# DUObot.net
KiCad netlist of a schematic drawn in EAGLE
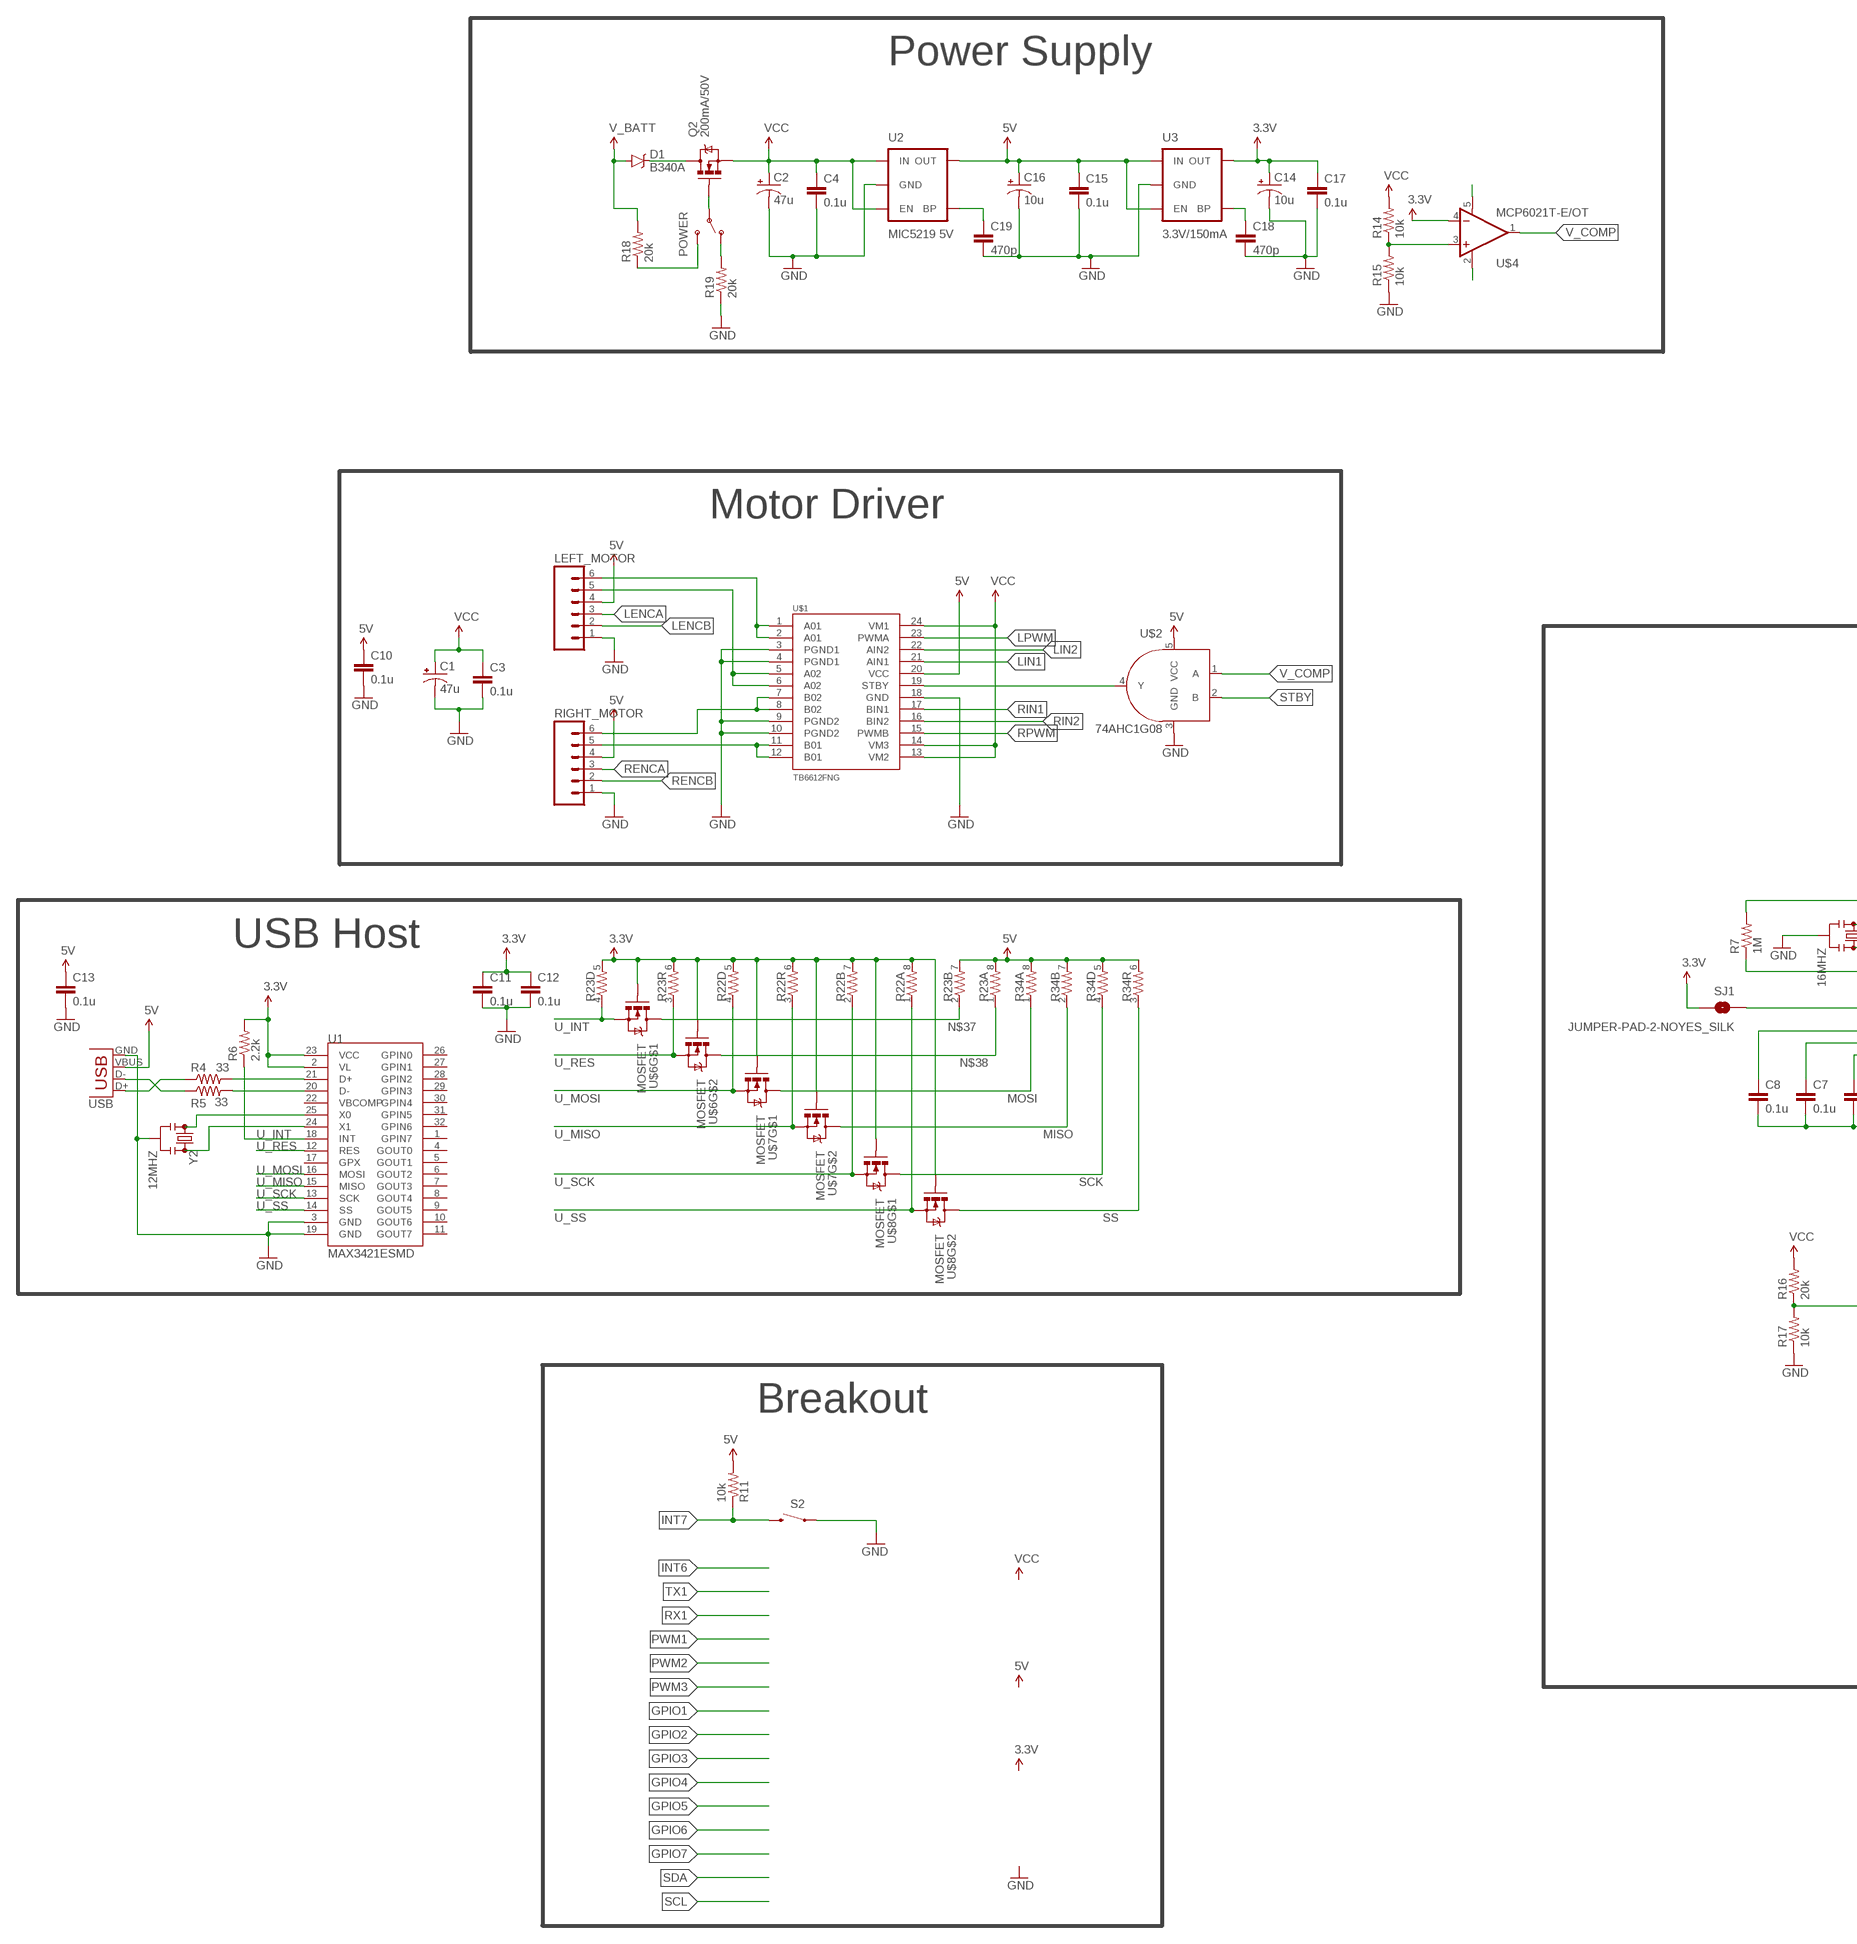
[diagram p0: schematic, sheet 1, part 1 of 2]
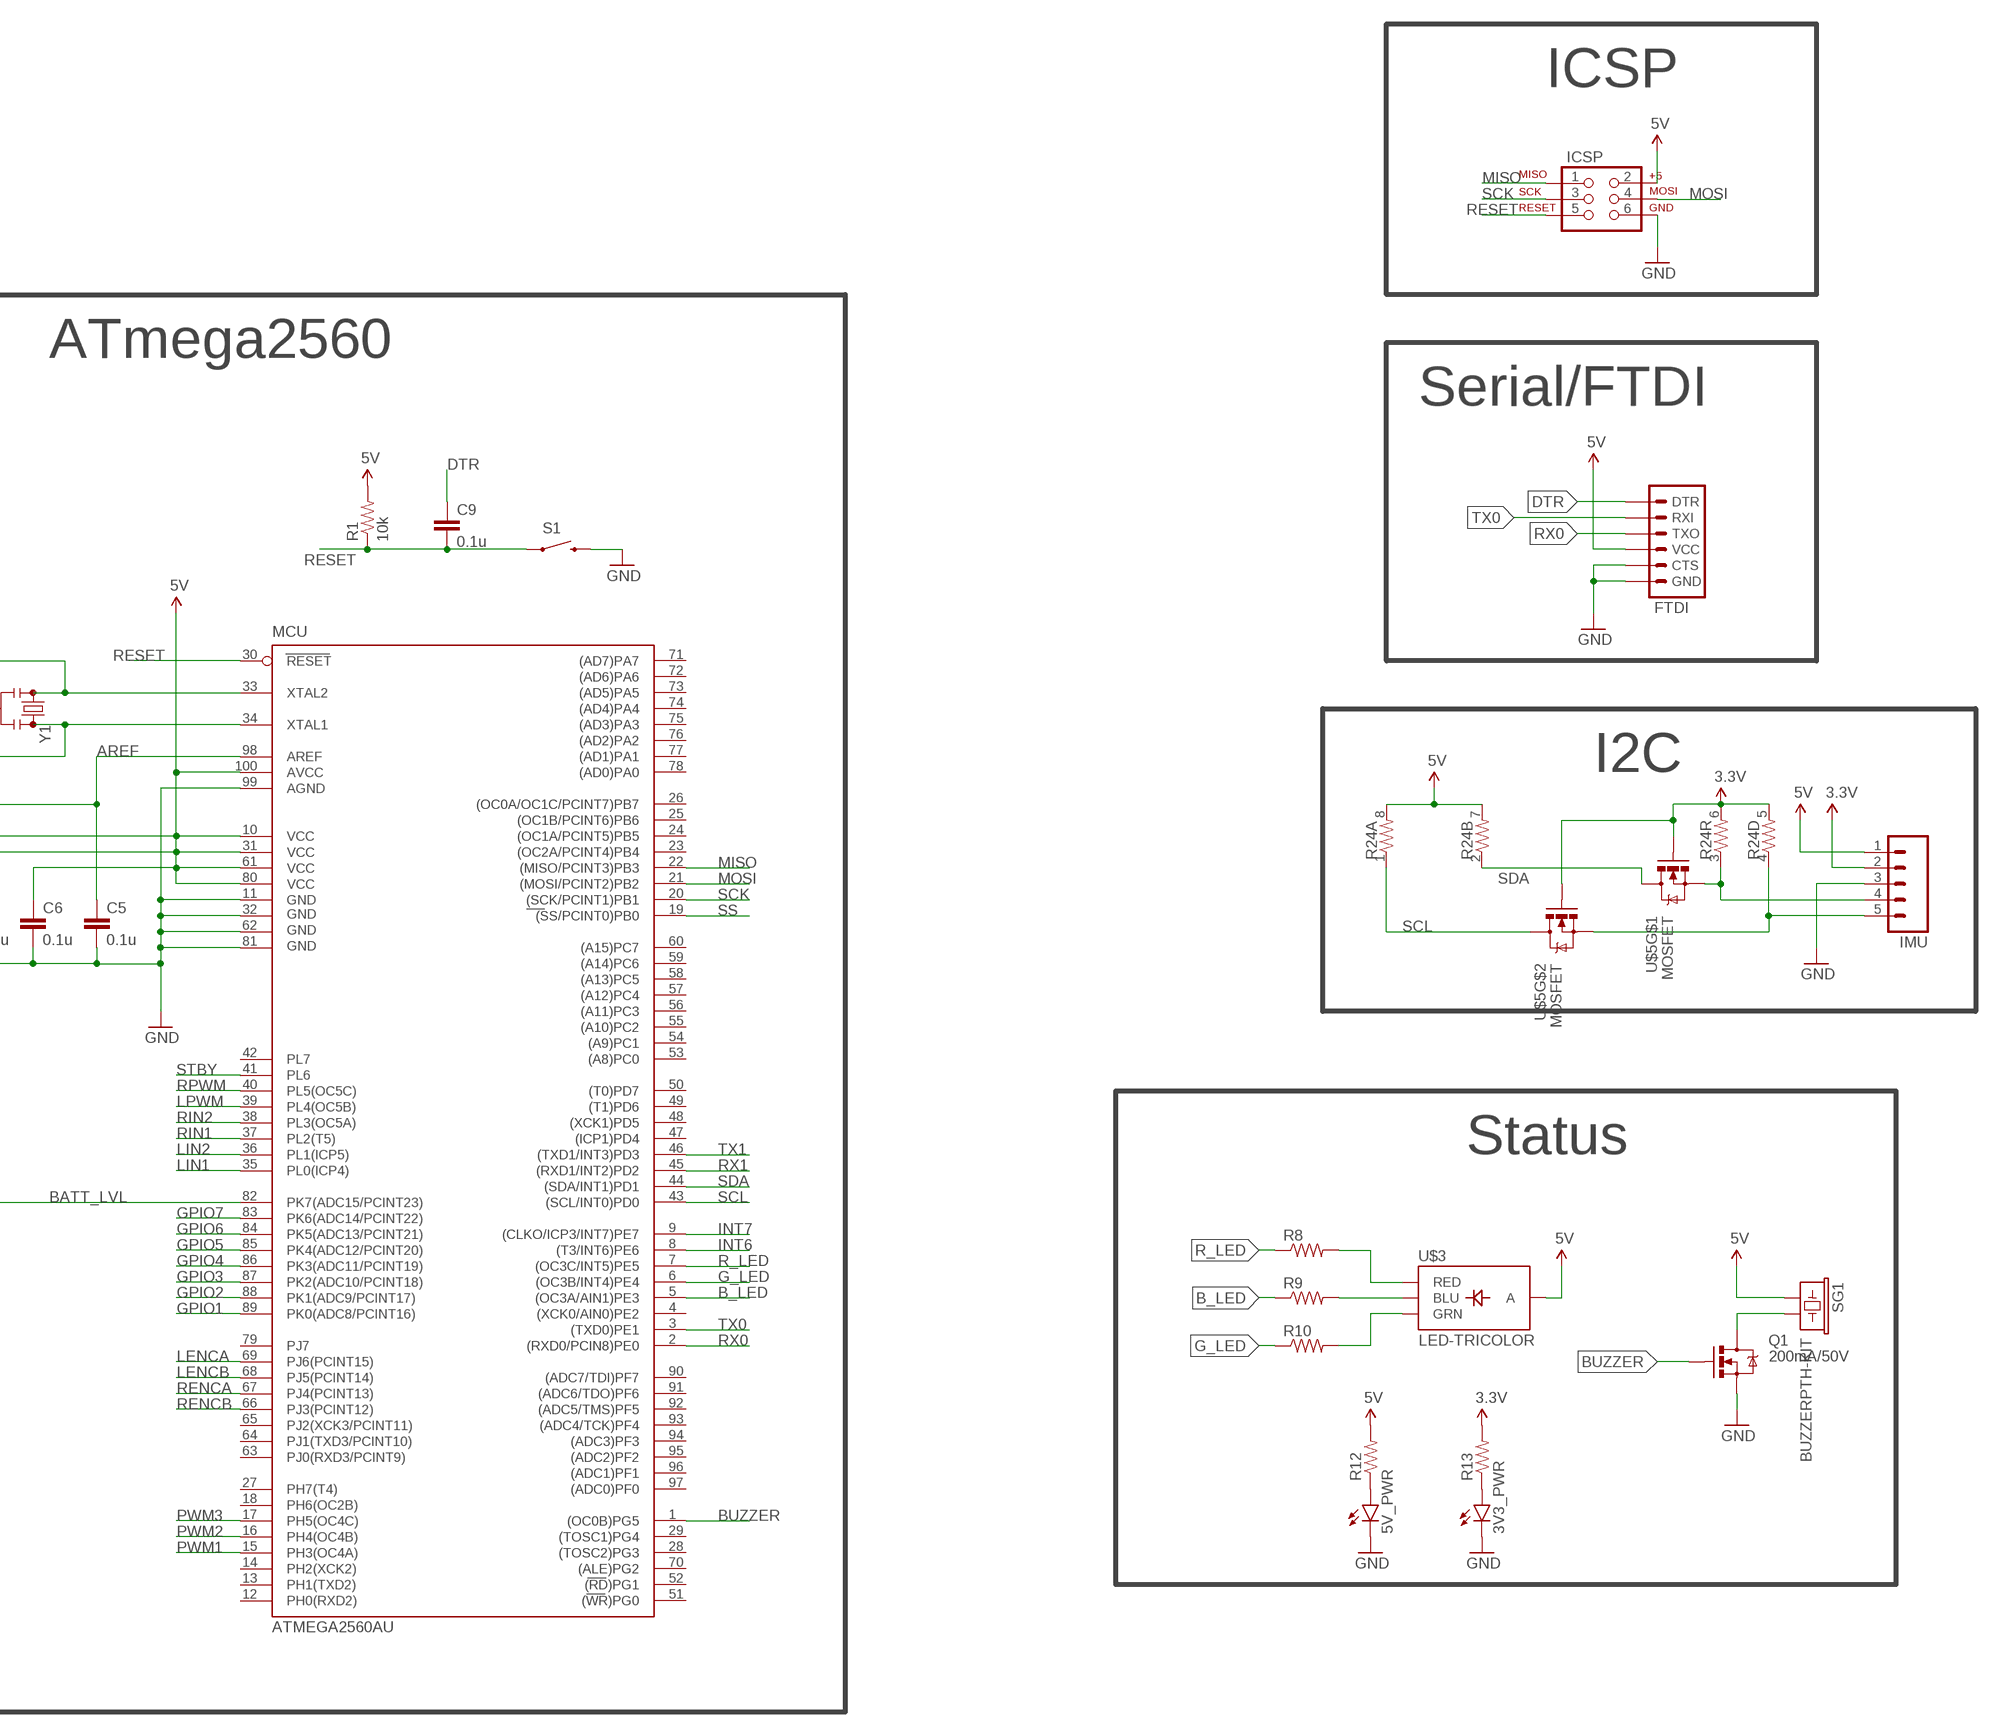
[diagram p1: schematic, sheet 1, part 2 of 2]

(export (version "E")
  (design (tool "Eeschema 10.0.6"))
  (components
    (comp (ref "3V3_PWR")
      (value "LED0805")
      (footprint "eagle-import:LED-0805")
      (libsource (lib "eagle-import") (part "LED0805"))
    )
    (comp (ref "5V_PWR")
      (value "LED0805")
      (footprint "eagle-import:LED-0805")
      (libsource (lib "eagle-import") (part "LED0805"))
    )
    (comp (ref "C1")
      (value "47u")
      (footprint "eagle-import:PANASONIC_D")
      (libsource (lib "eagle-import") (part "CAP_POLD"))
    )
    (comp (ref "C2")
      (value "47u")
      (footprint "eagle-import:PANASONIC_D")
      (libsource (lib "eagle-import") (part "CAP_POLD"))
    )
    (comp (ref "C3")
      (value "0.1u")
      (footprint "eagle-import:0805")
      (libsource (lib "eagle-import") (part "CAP0805"))
    )
    (comp (ref "C4")
      (value "0.1u")
      (footprint "eagle-import:0805")
      (libsource (lib "eagle-import") (part "CAP0805"))
    )
    (comp (ref "C5")
      (value "0.1u")
      (footprint "eagle-import:0805")
      (libsource (lib "eagle-import") (part "CAP0805"))
    )
    (comp (ref "C6")
      (value "0.1u")
      (footprint "eagle-import:0805")
      (libsource (lib "eagle-import") (part "CAP0805"))
    )
    (comp (ref "C7")
      (value "0.1u")
      (footprint "eagle-import:0805")
      (libsource (lib "eagle-import") (part "CAP0805"))
    )
    (comp (ref "C8")
      (value "0.1u")
      (footprint "eagle-import:0805")
      (libsource (lib "eagle-import") (part "CAP0805"))
    )
    (comp (ref "C9")
      (value "0.1u")
      (footprint "eagle-import:0805")
      (libsource (lib "eagle-import") (part "CAP0805"))
    )
    (comp (ref "C10")
      (value "0.1u")
      (footprint "eagle-import:0805")
      (libsource (lib "eagle-import") (part "CAP0805"))
    )
    (comp (ref "C11")
      (value "0.1u")
      (footprint "eagle-import:0805")
      (libsource (lib "eagle-import") (part "CAP0805"))
    )
    (comp (ref "C12")
      (value "0.1u")
      (footprint "eagle-import:0805")
      (libsource (lib "eagle-import") (part "CAP0805"))
    )
    (comp (ref "C13")
      (value "0.1u")
      (footprint "eagle-import:0805")
      (libsource (lib "eagle-import") (part "CAP0805"))
    )
    (comp (ref "C14")
      (value "10u")
      (footprint "eagle-import:EIA3216")
      (libsource (lib "eagle-import") (part "SparkFun-Passives_CAP_POL1206"))
    )
    (comp (ref "C15")
      (value "0.1u")
      (footprint "eagle-import:0805")
      (libsource (lib "eagle-import") (part "CAP0805"))
    )
    (comp (ref "C16")
      (value "10u")
      (footprint "eagle-import:EIA3216")
      (libsource (lib "eagle-import") (part "SparkFun-Passives_CAP_POL1206"))
    )
    (comp (ref "C17")
      (value "0.1u")
      (footprint "eagle-import:0805")
      (libsource (lib "eagle-import") (part "CAP0805"))
    )
    (comp (ref "C18")
      (value "470p")
      (footprint "eagle-import:0805")
      (libsource (lib "eagle-import") (part "CAP0805"))
    )
    (comp (ref "C19")
      (value "470p")
      (footprint "eagle-import:0805")
      (libsource (lib "eagle-import") (part "CAP0805"))
    )
    (comp (ref "D1")
      (value "B340A")
      (footprint "eagle-import:SMA-DIODE")
      (libsource (lib "eagle-import") (part "DIODE-SCHOTTKY-B340A"))
    )
    (comp (ref "FTDI")
      (value "ARDUINO_SERIAL_PROGRAMPTH")
      (footprint "eagle-import:1X06")
      (libsource (lib "eagle-import") (part "ARDUINO_SERIAL_PROGRAMPTH"))
    )
    (comp (ref "ICSP")
      (value "AVR_SPI_PRG_6TESTPOINTS")
      (footprint "eagle-import:2X3_TEST_POINTS")
      (libsource (lib "eagle-import") (part "AVR_SPI_PRG_6TESTPOINTS"))
    )
    (comp (ref "IMU")
      (value "M05SMD2")
      (footprint "eagle-import:1X05-1MM-RA")
      (libsource (lib "eagle-import") (part "M05SMD2"))
    )
    (comp (ref "LEFT_MOTOR")
      (value "M06SMD-1MM")
      (footprint "eagle-import:1X06-1MM")
      (libsource (lib "eagle-import") (part "M06SMD-1MM"))
    )
    (comp (ref "MCU")
      (value "ATMEGA2560AU")
      (footprint "eagle-import:TQFP100")
      (libsource (lib "eagle-import") (part "ATMEGA2560AU"))
    )
    (comp (ref "POWER")
      (value "SWITCH-SPDT-SMD-A")
      (footprint "eagle-import:SWITCH-SPST-SMD-A")
      (libsource (lib "eagle-import") (part "SWITCH-SPDT-SMD-A"))
    )
    (comp (ref "Q1")
      (value "200mA/50V")
      (footprint "eagle-import:SOT23-3")
      (libsource (lib "eagle-import") (part "MOSFET-NCHANNELBSS138"))
    )
    (comp (ref "Q2")
      (value "200mA/50V")
      (footprint "eagle-import:SOT23-3")
      (libsource (lib "eagle-import") (part "MOSFET-NCHANNELBSS138"))
    )
    (comp (ref "R1")
      (value "10k")
      (footprint "eagle-import:0805")
      (libsource (lib "eagle-import") (part "RESISTOR0805-RES"))
    )
    (comp (ref "R4")
      (value "33")
      (footprint "eagle-import:0805")
      (libsource (lib "eagle-import") (part "RESISTOR0805-RES"))
    )
    (comp (ref "R5")
      (value "33")
      (footprint "eagle-import:0805")
      (libsource (lib "eagle-import") (part "RESISTOR0805-RES"))
    )
    (comp (ref "R6")
      (value "2.2k")
      (footprint "eagle-import:0805")
      (libsource (lib "eagle-import") (part "RESISTOR0805-RES"))
    )
    (comp (ref "R7")
      (value "1M")
      (footprint "eagle-import:0805")
      (libsource (lib "eagle-import") (part "RESISTOR0805-RES"))
    )
    (comp (ref "R8")
      (value "RESISTOR0805-RES")
      (footprint "eagle-import:0805")
      (libsource (lib "eagle-import") (part "RESISTOR0805-RES"))
    )
    (comp (ref "R9")
      (value "RESISTOR0805-RES")
      (footprint "eagle-import:0805")
      (libsource (lib "eagle-import") (part "RESISTOR0805-RES"))
    )
    (comp (ref "R10")
      (value "RESISTOR0805-RES")
      (footprint "eagle-import:0805")
      (libsource (lib "eagle-import") (part "RESISTOR0805-RES"))
    )
    (comp (ref "R11")
      (value "10k")
      (footprint "eagle-import:0805")
      (libsource (lib "eagle-import") (part "RESISTOR0805-RES"))
    )
    (comp (ref "R12")
      (value "RESISTOR0805-RES")
      (footprint "eagle-import:0805")
      (libsource (lib "eagle-import") (part "RESISTOR0805-RES"))
    )
    (comp (ref "R13")
      (value "RESISTOR0805-RES")
      (footprint "eagle-import:0805")
      (libsource (lib "eagle-import") (part "RESISTOR0805-RES"))
    )
    (comp (ref "R14")
      (value "10k")
      (footprint "eagle-import:0805")
      (libsource (lib "eagle-import") (part "RESISTOR0805-RES"))
    )
    (comp (ref "R15")
      (value "10k")
      (footprint "eagle-import:0805")
      (libsource (lib "eagle-import") (part "RESISTOR0805-RES"))
    )
    (comp (ref "R16")
      (value "20k")
      (footprint "eagle-import:0805")
      (libsource (lib "eagle-import") (part "RESISTOR0805-RES"))
    )
    (comp (ref "R17")
      (value "10k")
      (footprint "eagle-import:0805")
      (libsource (lib "eagle-import") (part "RESISTOR0805-RES"))
    )
    (comp (ref "R18")
      (value "20k")
      (footprint "eagle-import:0805")
      (libsource (lib "eagle-import") (part "RESISTOR0805-RES"))
    )
    (comp (ref "R19")
      (value "20k")
      (footprint "eagle-import:0805")
      (libsource (lib "eagle-import") (part "RESISTOR0805-RES"))
    )
    (comp (ref "R22")
      (value "RESISTOR-ARRAY0603-ARV")
      (footprint "eagle-import:0603-ARV")
      (libsource (lib "eagle-import") (part "RESISTOR-ARRAY0603-ARV"))
    )
    (comp (ref "R23")
      (value "RESISTOR-ARRAY0603-ARV")
      (footprint "eagle-import:0603-ARV")
      (libsource (lib "eagle-import") (part "RESISTOR-ARRAY0603-ARV"))
    )
    (comp (ref "R24")
      (value "RESISTOR-ARRAY0603-ARV")
      (footprint "eagle-import:0603-ARV")
      (libsource (lib "eagle-import") (part "RESISTOR-ARRAY0603-ARV"))
    )
    (comp (ref "R34")
      (value "RESISTOR-ARRAY0603-ARV")
      (footprint "eagle-import:0603-ARV")
      (libsource (lib "eagle-import") (part "RESISTOR-ARRAY0603-ARV"))
    )
    (comp (ref "RIGHT_MOTOR")
      (value "M06SMD-1MM")
      (footprint "eagle-import:1X06-1MM")
      (libsource (lib "eagle-import") (part "M06SMD-1MM"))
    )
    (comp (ref "S1")
      (value "SWITCH-MOMENTARY-2SMD-4")
      (footprint "eagle-import:TACTILE_SWITCH_TALL")
      (libsource (lib "eagle-import") (part "SWITCH-MOMENTARY-2SMD-4"))
    )
    (comp (ref "S2")
      (value "SWITCH-MOMENTARY-2SMD-4")
      (footprint "eagle-import:TACTILE_SWITCH_TALL")
      (libsource (lib "eagle-import") (part "SWITCH-MOMENTARY-2SMD-4"))
    )
    (comp (ref "SG1")
      (value "BUZZERPTH-KIT")
      (footprint "eagle-import:BUZZER-12MM-KIT")
      (libsource (lib "eagle-import") (part "BUZZERPTH-KIT"))
    )
    (comp (ref "SJ1")
      (value "JUMPER-PAD-2-NOYES_SILK")
      (footprint "eagle-import:PAD-JUMPER-2-NO_YES_SILK")
      (libsource (lib "eagle-import") (part "JUMPER-PAD-2-NOYES_SILK"))
    )
    (comp (ref "U$1")
      (value "TB6612FNG")
      (footprint "eagle-import:SSOP24")
      (libsource (lib "eagle-import") (part "TB6612FNG"))
    )
    (comp (ref "U$2")
      (value "74AHC1G08")
      (footprint "eagle-import:SOT353")
      (libsource (lib "eagle-import") (part "74AHC1G08"))
    )
    (comp (ref "U$3")
      (value "LED-TRICOLOR")
      (footprint "eagle-import:LED-TRICOLOR-SMD")
      (libsource (lib "eagle-import") (part "LED-TRICOLOR"))
    )
    (comp (ref "U$4")
      (value "MCP6021T-E/OT")
      (footprint "eagle-import:SOT23-5")
      (libsource (lib "eagle-import") (part "MCP6021T-E/OT"))
    )
    (comp (ref "U$5")
      (value "MOSFET")
      (footprint "eagle-import:SOT363_V2")
      (libsource (lib "eagle-import") (part "MOSFET"))
    )
    (comp (ref "U$6")
      (value "MOSFET")
      (footprint "eagle-import:SOT363_V2")
      (libsource (lib "eagle-import") (part "MOSFET"))
    )
    (comp (ref "U$7")
      (value "MOSFET")
      (footprint "eagle-import:SOT363_V2")
      (libsource (lib "eagle-import") (part "MOSFET"))
    )
    (comp (ref "U$8")
      (value "MOSFET")
      (footprint "eagle-import:SOT363_V2")
      (libsource (lib "eagle-import") (part "MOSFET"))
    )
    (comp (ref "U1")
      (value "MAX3421ESMD")
      (footprint "eagle-import:TQFP32-5MM")
      (libsource (lib "eagle-import") (part "MAX3421ESMD"))
    )
    (comp (ref "U2")
      (value "MIC5219 5V")
      (footprint "eagle-import:SOT23-5")
      (libsource (lib "eagle-import") (part "V_REG_MIC52195V"))
    )
    (comp (ref "U3")
      (value "3.3V/150mA")
      (footprint "eagle-import:SOT23-5")
      (libsource (lib "eagle-import") (part "V_REG_MIC52053.3V"))
    )
    (comp (ref "USB")
      (value "USB-A-SMD")
      (footprint "eagle-import:USB-A-S-NOSILK-FEMALE")
      (libsource (lib "eagle-import") (part "USB-A-SMD"))
    )
    (comp (ref "Y1")
      (value "16MHZ")
      (footprint "eagle-import:RESONATOR-SMD")
      (libsource (lib "eagle-import") (part "RESONATOR16MHZ"))
    )
    (comp (ref "Y2")
      (value "12MHZ")
      (footprint "eagle-import:RESONATOR-SMD")
      (libsource (lib "eagle-import") (part "RESONATOR16MHZ"))
    )
  )
  (nets
    (net (code "1") (name "/AREF") (class "Default")
      (node (ref "C5") (pin "1") (pinfunction "1_1") (pintype "passive"))
      (node (ref "MCU") (pin "98") (pinfunction "AREF_98") (pintype "bidirectional"))
      (node (ref "SJ1") (pin "1") (pinfunction "1_1") (pintype "passive"))
    )
    (net (code "2") (name "/BATT_LVL") (class "Default")
      (node (ref "MCU") (pin "82") (pinfunction "PK7(ADC15/PCINT23)_82") (pintype "bidirectional"))
      (node (ref "R16") (pin "1") (pinfunction "1_1") (pintype "passive"))
      (node (ref "R17") (pin "2") (pinfunction "2_2") (pintype "passive"))
    )
    (net (code "3") (name "/MISO") (class "Default")
      (node (ref "ICSP") (pin "1") (pinfunction "1_1") (pintype "passive"))
      (node (ref "MCU") (pin "22") (pinfunction "(MISO/PCINT3)PB3_22") (pintype "bidirectional"))
      (node (ref "R34") (pin "2") (pinfunction "1_2") (pintype "passive"))
      (node (ref "U$7") (pin "D2") (pinfunction "D_D2") (pintype "passive"))
    )
    (net (code "4") (name "/MOSI") (class "Default")
      (node (ref "ICSP") (pin "4") (pinfunction "4_4") (pintype "passive"))
      (node (ref "MCU") (pin "21") (pinfunction "(MOSI/PCINT2)PB2_21") (pintype "bidirectional"))
      (node (ref "R34") (pin "1") (pinfunction "1_1") (pintype "passive"))
      (node (ref "U$7") (pin "D1") (pinfunction "D_D1") (pintype "passive"))
    )
    (net (code "5") (name "/N$37") (class "Default")
      (node (ref "R23") (pin "2") (pinfunction "1_2") (pintype "passive"))
      (node (ref "U$6") (pin "D1") (pinfunction "D_D1") (pintype "passive"))
    )
    (net (code "6") (name "/N$38") (class "Default")
      (node (ref "R23") (pin "1") (pinfunction "1_1") (pintype "passive"))
      (node (ref "U$6") (pin "D2") (pinfunction "D_D2") (pintype "passive"))
    )
    (net (code "7") (name "/RESET") (class "Default")
      (node (ref "C9") (pin "2") (pinfunction "2_2") (pintype "passive"))
      (node (ref "ICSP") (pin "5") (pinfunction "5_5") (pintype "passive"))
      (node (ref "MCU") (pin "30") (pinfunction "RESET_30") (pintype "input"))
      (node (ref "R1") (pin "1") (pinfunction "1_1") (pintype "passive"))
      (node (ref "S1") (pin "A2") (pinfunction "1_A2") (pintype "passive"))
    )
    (net (code "8") (name "/SCK") (class "Default")
      (node (ref "ICSP") (pin "3") (pinfunction "3_3") (pintype "passive"))
      (node (ref "MCU") (pin "20") (pinfunction "(SCK/PCINT1)PB1_20") (pintype "bidirectional"))
      (node (ref "R34") (pin "4") (pinfunction "1_4") (pintype "passive"))
      (node (ref "U$8") (pin "D1") (pinfunction "D_D1") (pintype "passive"))
    )
    (net (code "9") (name "/SS") (class "Default")
      (node (ref "MCU") (pin "19") (pinfunction "(SS/PCINT0)PB0_19") (pintype "bidirectional"))
      (node (ref "R34") (pin "3") (pinfunction "1_3") (pintype "passive"))
      (node (ref "U$8") (pin "D2") (pinfunction "D_D2") (pintype "passive"))
    )
    (net (code "10") (name "/U_INT") (class "Default")
      (node (ref "R23") (pin "4") (pinfunction "1_4") (pintype "passive"))
      (node (ref "R6") (pin "1") (pinfunction "1_1") (pintype "passive"))
      (node (ref "U$6") (pin "S1") (pinfunction "S_S1") (pintype "passive"))
      (node (ref "U1") (pin "18") (pinfunction "INT_18") (pintype "bidirectional"))
    )
    (net (code "11") (name "/U_MISO") (class "Default")
      (node (ref "R22") (pin "3") (pinfunction "1_3") (pintype "passive"))
      (node (ref "U$7") (pin "S2") (pinfunction "S_S2") (pintype "passive"))
      (node (ref "U1") (pin "15") (pinfunction "MISO_15") (pintype "bidirectional"))
    )
    (net (code "12") (name "/U_MOSI") (class "Default")
      (node (ref "R22") (pin "4") (pinfunction "1_4") (pintype "passive"))
      (node (ref "U$7") (pin "S1") (pinfunction "S_S1") (pintype "passive"))
      (node (ref "U1") (pin "16") (pinfunction "MOSI_16") (pintype "bidirectional"))
    )
    (net (code "13") (name "/U_RES") (class "Default")
      (node (ref "R23") (pin "3") (pinfunction "1_3") (pintype "passive"))
      (node (ref "U$6") (pin "S2") (pinfunction "S_S2") (pintype "passive"))
      (node (ref "U1") (pin "12") (pinfunction "RES_12") (pintype "bidirectional"))
    )
    (net (code "14") (name "/U_SCK") (class "Default")
      (node (ref "R22") (pin "2") (pinfunction "1_2") (pintype "passive"))
      (node (ref "U$8") (pin "S1") (pinfunction "S_S1") (pintype "passive"))
      (node (ref "U1") (pin "13") (pinfunction "SCK_13") (pintype "bidirectional"))
    )
    (net (code "15") (name "/U_SS") (class "Default")
      (node (ref "R22") (pin "1") (pinfunction "1_1") (pintype "passive"))
      (node (ref "U$8") (pin "S2") (pinfunction "S_S2") (pintype "passive"))
      (node (ref "U1") (pin "14") (pinfunction "SS_14") (pintype "bidirectional"))
    )
    (net (code "16") (name "3.3V") (class "Default")
      (node (ref "C11") (pin "1") (pinfunction "1_1") (pintype "passive"))
      (node (ref "C12") (pin "1") (pinfunction "1_1") (pintype "passive"))
      (node (ref "C14") (pin "A") (pinfunction "+_A") (pintype "passive"))
      (node (ref "C17") (pin "1") (pinfunction "1_1") (pintype "passive"))
      (node (ref "IMU") (pin "2") (pinfunction "2_2") (pintype "passive"))
      (node (ref "R13") (pin "2") (pinfunction "2_2") (pintype "passive"))
      (node (ref "R22") (pin "5") (pinfunction "2_5") (pintype "passive"))
      (node (ref "R22") (pin "6") (pinfunction "2_6") (pintype "passive"))
      (node (ref "R22") (pin "7") (pinfunction "2_7") (pintype "passive"))
      (node (ref "R22") (pin "8") (pinfunction "2_8") (pintype "passive"))
      (node (ref "R23") (pin "5") (pinfunction "2_5") (pintype "passive"))
      (node (ref "R23") (pin "6") (pinfunction "2_6") (pintype "passive"))
      (node (ref "R24") (pin "5") (pinfunction "2_5") (pintype "passive"))
      (node (ref "R24") (pin "6") (pinfunction "2_6") (pintype "passive"))
      (node (ref "R6") (pin "2") (pinfunction "2_2") (pintype "passive"))
      (node (ref "SJ1") (pin "2") (pinfunction "2_2") (pintype "passive"))
      (node (ref "U$4") (pin "4") (pinfunction "-IN_4") (pintype "input"))
      (node (ref "U$5") (pin "G1") (pinfunction "G_G1") (pintype "passive"))
      (node (ref "U$5") (pin "G2") (pinfunction "G_G2") (pintype "passive"))
      (node (ref "U$6") (pin "G1") (pinfunction "G_G1") (pintype "passive"))
      (node (ref "U$6") (pin "G2") (pinfunction "G_G2") (pintype "passive"))
      (node (ref "U$7") (pin "G1") (pinfunction "G_G1") (pintype "passive"))
      (node (ref "U$7") (pin "G2") (pinfunction "G_G2") (pintype "passive"))
      (node (ref "U$8") (pin "G1") (pinfunction "G_G1") (pintype "passive"))
      (node (ref "U$8") (pin "G2") (pinfunction "G_G2") (pintype "passive"))
      (node (ref "U1") (pin "2") (pinfunction "VL_2") (pintype "bidirectional"))
      (node (ref "U1") (pin "23") (pinfunction "VCC_23") (pintype "bidirectional"))
      (node (ref "U3") (pin "5") (pinfunction "OUT_5") (pintype "passive"))
    )
    (net (code "17") (name "5V") (class "Default")
      (node (ref "C10") (pin "1") (pinfunction "1_1") (pintype "passive"))
      (node (ref "C13") (pin "1") (pinfunction "1_1") (pintype "passive"))
      (node (ref "C15") (pin "1") (pinfunction "1_1") (pintype "passive"))
      (node (ref "C16") (pin "A") (pinfunction "+_A") (pintype "passive"))
      (node (ref "C6") (pin "1") (pinfunction "1_1") (pintype "passive"))
      (node (ref "C7") (pin "1") (pinfunction "1_1") (pintype "passive"))
      (node (ref "C8") (pin "1") (pinfunction "1_1") (pintype "passive"))
      (node (ref "FTDI") (pin "4") (pinfunction "VCC_4") (pintype "passive"))
      (node (ref "ICSP") (pin "2") (pinfunction "2_2") (pintype "passive"))
      (node (ref "IMU") (pin "1") (pinfunction "1_1") (pintype "passive"))
      (node (ref "LEFT_MOTOR") (pin "4") (pinfunction "4_4") (pintype "passive"))
      (node (ref "MCU") (pin "10") (pinfunction "VCC_10") (pintype "power_in"))
      (node (ref "MCU") (pin "100") (pinfunction "AVCC_100") (pintype "power_in"))
      (node (ref "MCU") (pin "31") (pinfunction "VCC1_31") (pintype "power_in"))
      (node (ref "MCU") (pin "61") (pinfunction "VCC2_61") (pintype "power_in"))
      (node (ref "MCU") (pin "80") (pinfunction "VCC3_80") (pintype "power_in"))
      (node (ref "R1") (pin "2") (pinfunction "2_2") (pintype "passive"))
      (node (ref "R11") (pin "2") (pinfunction "2_2") (pintype "passive"))
      (node (ref "R12") (pin "2") (pinfunction "2_2") (pintype "passive"))
      (node (ref "R23") (pin "7") (pinfunction "2_7") (pintype "passive"))
      (node (ref "R23") (pin "8") (pinfunction "2_8") (pintype "passive"))
      (node (ref "R24") (pin "7") (pinfunction "2_7") (pintype "passive"))
      (node (ref "R24") (pin "8") (pinfunction "2_8") (pintype "passive"))
      (node (ref "R34") (pin "5") (pinfunction "2_5") (pintype "passive"))
      (node (ref "R34") (pin "6") (pinfunction "2_6") (pintype "passive"))
      (node (ref "R34") (pin "7") (pinfunction "2_7") (pintype "passive"))
      (node (ref "R34") (pin "8") (pinfunction "2_8") (pintype "passive"))
      (node (ref "RIGHT_MOTOR") (pin "4") (pinfunction "4_4") (pintype "passive"))
      (node (ref "SG1") (pin "+") (pinfunction "1_+") (pintype "passive"))
      (node (ref "U$1") (pin "20") (pinfunction "VCC_20") (pintype "bidirectional"))
      (node (ref "U$2") (pin "5") (pinfunction "VCC_5") (pintype "bidirectional"))
      (node (ref "U$3") (pin "A") (pinfunction "A_A") (pintype "bidirectional"))
      (node (ref "U2") (pin "5") (pinfunction "OUT_5") (pintype "passive"))
      (node (ref "U3") (pin "1") (pinfunction "IN_1") (pintype "input"))
      (node (ref "U3") (pin "3") (pinfunction "EN_3") (pintype "input"))
      (node (ref "USB") (pin "VBUS") (pinfunction "VBUS_VBUS") (pintype "bidirectional"))
    )
    (net (code "18") (name "BUZZER") (class "Default")
      (node (ref "MCU") (pin "1") (pinfunction "(OC0B)PG5_1") (pintype "bidirectional"))
      (node (ref "Q1") (pin "1") (pinfunction "G_1") (pintype "passive"))
    )
    (net (code "19") (name "B_LED") (class "Default")
      (node (ref "MCU") (pin "5") (pinfunction "(OC3A/AIN1)PE3_5") (pintype "bidirectional"))
      (node (ref "R9") (pin "1") (pinfunction "1_1") (pintype "passive"))
    )
    (net (code "20") (name "DTR") (class "Default")
      (node (ref "C9") (pin "1") (pinfunction "1_1") (pintype "passive"))
      (node (ref "FTDI") (pin "1") (pinfunction "DTR_1") (pintype "passive"))
    )
    (net (code "21") (name "GND") (class "Default")
      (node (ref "3V3_PWR") (pin "CATHODE") (pinfunction "C_CATHODE") (pintype "passive"))
      (node (ref "5V_PWR") (pin "CATHODE") (pinfunction "C_CATHODE") (pintype "passive"))
      (node (ref "C1") (pin "-") (pinfunction "-_-") (pintype "passive"))
      (node (ref "C10") (pin "2") (pinfunction "2_2") (pintype "passive"))
      (node (ref "C11") (pin "2") (pinfunction "2_2") (pintype "passive"))
      (node (ref "C12") (pin "2") (pinfunction "2_2") (pintype "passive"))
      (node (ref "C13") (pin "2") (pinfunction "2_2") (pintype "passive"))
      (node (ref "C14") (pin "C") (pinfunction "-_C") (pintype "passive"))
      (node (ref "C15") (pin "2") (pinfunction "2_2") (pintype "passive"))
      (node (ref "C16") (pin "C") (pinfunction "-_C") (pintype "passive"))
      (node (ref "C17") (pin "2") (pinfunction "2_2") (pintype "passive"))
      (node (ref "C18") (pin "2") (pinfunction "2_2") (pintype "passive"))
      (node (ref "C19") (pin "2") (pinfunction "2_2") (pintype "passive"))
      (node (ref "C2") (pin "-") (pinfunction "-_-") (pintype "passive"))
      (node (ref "C3") (pin "2") (pinfunction "2_2") (pintype "passive"))
      (node (ref "C4") (pin "2") (pinfunction "2_2") (pintype "passive"))
      (node (ref "C5") (pin "2") (pinfunction "2_2") (pintype "passive"))
      (node (ref "C6") (pin "2") (pinfunction "2_2") (pintype "passive"))
      (node (ref "C7") (pin "2") (pinfunction "2_2") (pintype "passive"))
      (node (ref "C8") (pin "2") (pinfunction "2_2") (pintype "passive"))
      (node (ref "FTDI") (pin "5") (pinfunction "CTS_5") (pintype "passive"))
      (node (ref "FTDI") (pin "6") (pinfunction "GND_6") (pintype "passive"))
      (node (ref "ICSP") (pin "6") (pinfunction "6_6") (pintype "passive"))
      (node (ref "IMU") (pin "3") (pinfunction "3_3") (pintype "passive"))
      (node (ref "LEFT_MOTOR") (pin "1") (pinfunction "1_1") (pintype "passive"))
      (node (ref "MCU") (pin "11") (pinfunction "GND_11") (pintype "power_in"))
      (node (ref "MCU") (pin "32") (pinfunction "GND1_32") (pintype "power_in"))
      (node (ref "MCU") (pin "62") (pinfunction "GND2_62") (pintype "power_in"))
      (node (ref "MCU") (pin "81") (pinfunction "GND3_81") (pintype "power_in"))
      (node (ref "MCU") (pin "99") (pinfunction "AGND_99") (pintype "power_in"))
      (node (ref "Q1") (pin "2") (pinfunction "S_2") (pintype "passive"))
      (node (ref "R15") (pin "1") (pinfunction "1_1") (pintype "passive"))
      (node (ref "R17") (pin "1") (pinfunction "1_1") (pintype "passive"))
      (node (ref "R19") (pin "1") (pinfunction "1_1") (pintype "passive"))
      (node (ref "RIGHT_MOTOR") (pin "1") (pinfunction "1_1") (pintype "passive"))
      (node (ref "S1") (pin "B2") (pinfunction "2_B2") (pintype "passive"))
      (node (ref "S2") (pin "A2") (pinfunction "1_A2") (pintype "passive"))
      (node (ref "U$1") (pin "10") (pinfunction "PGND2_10") (pintype "bidirectional"))
      (node (ref "U$1") (pin "18") (pinfunction "GND_18") (pintype "bidirectional"))
      (node (ref "U$1") (pin "3") (pinfunction "PGND1_3") (pintype "bidirectional"))
      (node (ref "U$1") (pin "4") (pinfunction "PGND1_4") (pintype "bidirectional"))
      (node (ref "U$1") (pin "9") (pinfunction "PGND2_9") (pintype "bidirectional"))
      (node (ref "U$2") (pin "3") (pinfunction "GND_3") (pintype "bidirectional"))
      (node (ref "U1") (pin "19") (pinfunction "GND_19") (pintype "bidirectional"))
      (node (ref "U1") (pin "3") (pinfunction "GND_3") (pintype "bidirectional"))
      (node (ref "U2") (pin "2") (pinfunction "GND_2") (pintype "input"))
      (node (ref "U3") (pin "2") (pinfunction "GND_2") (pintype "input"))
      (node (ref "USB") (pin "GND") (pinfunction "GND_GND") (pintype "bidirectional"))
      (node (ref "Y1") (pin "2") (pinfunction "2_2") (pintype "passive"))
      (node (ref "Y2") (pin "2") (pinfunction "2_2") (pintype "passive"))
    )
    (net (code "22") (name "GPIO1") (class "Default")
      (node (ref "MCU") (pin "89") (pinfunction "PK0(ADC8/PCINT16)_89") (pintype "bidirectional"))
    )
    (net (code "23") (name "GPIO2") (class "Default")
      (node (ref "MCU") (pin "88") (pinfunction "PK1(ADC9/PCINT17)_88") (pintype "bidirectional"))
    )
    (net (code "24") (name "GPIO3") (class "Default")
      (node (ref "MCU") (pin "87") (pinfunction "PK2(ADC10/PCINT18)_87") (pintype "bidirectional"))
    )
    (net (code "25") (name "GPIO4") (class "Default")
      (node (ref "MCU") (pin "86") (pinfunction "PK3(ADC11/PCINT19)_86") (pintype "bidirectional"))
    )
    (net (code "26") (name "GPIO5") (class "Default")
      (node (ref "MCU") (pin "85") (pinfunction "PK4(ADC12/PCINT20)_85") (pintype "bidirectional"))
    )
    (net (code "27") (name "GPIO6") (class "Default")
      (node (ref "MCU") (pin "84") (pinfunction "PK5(ADC13/PCINT21)_84") (pintype "bidirectional"))
    )
    (net (code "28") (name "GPIO7") (class "Default")
      (node (ref "MCU") (pin "83") (pinfunction "PK6(ADC14/PCINT22)_83") (pintype "bidirectional"))
    )
    (net (code "29") (name "G_LED") (class "Default")
      (node (ref "MCU") (pin "6") (pinfunction "(OC3B/INT4)PE4_6") (pintype "bidirectional"))
      (node (ref "R10") (pin "1") (pinfunction "1_1") (pintype "passive"))
    )
    (net (code "30") (name "INT6") (class "Default")
      (node (ref "MCU") (pin "8") (pinfunction "(T3/INT6)PE6_8") (pintype "bidirectional"))
    )
    (net (code "31") (name "INT7") (class "Default")
      (node (ref "MCU") (pin "9") (pinfunction "(CLKO/ICP3/INT7)PE7_9") (pintype "bidirectional"))
      (node (ref "R11") (pin "1") (pinfunction "1_1") (pintype "passive"))
      (node (ref "S2") (pin "B2") (pinfunction "2_B2") (pintype "passive"))
    )
    (net (code "32") (name "LENCA") (class "Default")
      (node (ref "LEFT_MOTOR") (pin "3") (pinfunction "3_3") (pintype "passive"))
      (node (ref "MCU") (pin "69") (pinfunction "PJ6(PCINT15)_69") (pintype "bidirectional"))
    )
    (net (code "33") (name "LENCB") (class "Default")
      (node (ref "LEFT_MOTOR") (pin "2") (pinfunction "2_2") (pintype "passive"))
      (node (ref "MCU") (pin "68") (pinfunction "PJ5(PCINT14)_68") (pintype "bidirectional"))
    )
    (net (code "34") (name "LIN1") (class "Default")
      (node (ref "MCU") (pin "35") (pinfunction "PL0(ICP4)_35") (pintype "bidirectional"))
      (node (ref "U$1") (pin "21") (pinfunction "AIN1_21") (pintype "bidirectional"))
    )
    (net (code "35") (name "LIN2") (class "Default")
      (node (ref "MCU") (pin "36") (pinfunction "PL1(ICP5)_36") (pintype "bidirectional"))
      (node (ref "U$1") (pin "22") (pinfunction "AIN2_22") (pintype "bidirectional"))
    )
    (net (code "36") (name "LPWM") (class "Default")
      (node (ref "MCU") (pin "39") (pinfunction "PL4(OC5B)_39") (pintype "bidirectional"))
      (node (ref "U$1") (pin "23") (pinfunction "PWMA_23") (pintype "bidirectional"))
    )
    (net (code "37") (name "Net-(3V3_PWR-A)") (class "Default")
      (node (ref "3V3_PWR") (pin "ANODE") (pinfunction "A_ANODE") (pintype "passive"))
      (node (ref "R13") (pin "1") (pinfunction "1_1") (pintype "passive"))
    )
    (net (code "38") (name "Net-(5V_PWR-A)") (class "Default")
      (node (ref "5V_PWR") (pin "ANODE") (pinfunction "A_ANODE") (pintype "passive"))
      (node (ref "R12") (pin "1") (pinfunction "1_1") (pintype "passive"))
    )
    (net (code "39") (name "Net-(LEFT_MOTOR-Pad5)") (class "Default")
      (node (ref "LEFT_MOTOR") (pin "5") (pinfunction "5_5") (pintype "passive"))
      (node (ref "U$1") (pin "5") (pinfunction "A02_5") (pintype "bidirectional"))
      (node (ref "U$1") (pin "6") (pinfunction "A02_6") (pintype "bidirectional"))
    )
    (net (code "40") (name "Net-(LEFT_MOTOR-Pad6)") (class "Default")
      (node (ref "LEFT_MOTOR") (pin "6") (pinfunction "6_6") (pintype "passive"))
      (node (ref "U$1") (pin "1") (pinfunction "A01_1") (pintype "bidirectional"))
      (node (ref "U$1") (pin "2") (pinfunction "A01_2") (pintype "bidirectional"))
    )
    (net (code "41") (name "Net-(MCU-XTAL1)") (class "Default")
      (node (ref "MCU") (pin "34") (pinfunction "XTAL1_34") (pintype "input"))
      (node (ref "R7") (pin "1") (pinfunction "1_1") (pintype "passive"))
      (node (ref "Y1") (pin "3") (pinfunction "3_3") (pintype "passive"))
    )
    (net (code "42") (name "Net-(MCU-XTAL2)") (class "Default")
      (node (ref "MCU") (pin "33") (pinfunction "XTAL2_33") (pintype "output"))
      (node (ref "R7") (pin "2") (pinfunction "2_2") (pintype "passive"))
      (node (ref "Y1") (pin "1") (pinfunction "1_1") (pintype "passive"))
    )
    (net (code "43") (name "Net-(POWER-O)") (class "Default")
      (node (ref "POWER") (pin "1") (pinfunction "O_1") (pintype "passive"))
      (node (ref "R19") (pin "2") (pinfunction "2_2") (pintype "passive"))
    )
    (net (code "44") (name "Net-(POWER-P)") (class "Default")
      (node (ref "POWER") (pin "2") (pinfunction "P_2") (pintype "passive"))
      (node (ref "Q2") (pin "1") (pinfunction "G_1") (pintype "passive"))
    )
    (net (code "45") (name "Net-(POWER-S)") (class "Default")
      (node (ref "POWER") (pin "3") (pinfunction "S_3") (pintype "passive"))
      (node (ref "R18") (pin "1") (pinfunction "1_1") (pintype "passive"))
    )
    (net (code "46") (name "Net-(Q1-D)") (class "Default")
      (node (ref "Q1") (pin "3") (pinfunction "D_3") (pintype "passive"))
      (node (ref "SG1") (pin "-") (pinfunction "2_-") (pintype "passive"))
    )
    (net (code "47") (name "Net-(Q2-D)") (class "Default")
      (node (ref "D1") (pin "C") (pinfunction "C_C") (pintype "passive"))
      (node (ref "Q2") (pin "3") (pinfunction "D_3") (pintype "passive"))
    )
    (net (code "48") (name "Net-(R4-Pad1)") (class "Default")
      (node (ref "R4") (pin "1") (pinfunction "1_1") (pintype "passive"))
      (node (ref "USB") (pin "D+") (pinfunction "D+_D+") (pintype "bidirectional"))
    )
    (net (code "49") (name "Net-(R5-Pad1)") (class "Default")
      (node (ref "R5") (pin "1") (pinfunction "1_1") (pintype "passive"))
      (node (ref "USB") (pin "D-") (pinfunction "D-_D-") (pintype "bidirectional"))
    )
    (net (code "50") (name "Net-(R24C-1)") (class "Default")
      (node (ref "IMU") (pin "5") (pinfunction "5_5") (pintype "passive"))
      (node (ref "R24") (pin "4") (pinfunction "1_4") (pintype "passive"))
      (node (ref "U$5") (pin "S2") (pinfunction "S_S2") (pintype "passive"))
    )
    (net (code "51") (name "Net-(R24D-1)") (class "Default")
      (node (ref "IMU") (pin "4") (pinfunction "4_4") (pintype "passive"))
      (node (ref "R24") (pin "3") (pinfunction "1_3") (pintype "passive"))
      (node (ref "U$5") (pin "S1") (pinfunction "S_S1") (pintype "passive"))
    )
    (net (code "52") (name "Net-(RIGHT_MOTOR-Pad5)") (class "Default")
      (node (ref "RIGHT_MOTOR") (pin "5") (pinfunction "5_5") (pintype "passive"))
      (node (ref "U$1") (pin "11") (pinfunction "B01_11") (pintype "bidirectional"))
      (node (ref "U$1") (pin "12") (pinfunction "B01_12") (pintype "bidirectional"))
    )
    (net (code "53") (name "Net-(RIGHT_MOTOR-Pad6)") (class "Default")
      (node (ref "RIGHT_MOTOR") (pin "6") (pinfunction "6_6") (pintype "passive"))
      (node (ref "U$1") (pin "7") (pinfunction "B02_7") (pintype "bidirectional"))
      (node (ref "U$1") (pin "8") (pinfunction "B02_8") (pintype "bidirectional"))
    )
    (net (code "54") (name "Net-(U$1-STBY)") (class "Default")
      (node (ref "U$1") (pin "19") (pinfunction "STBY_19") (pintype "bidirectional"))
      (node (ref "U$2") (pin "4") (pinfunction "Y_4") (pintype "bidirectional"))
    )
    (net (code "55") (name "Net-(U$3-BLU)") (class "Default")
      (node (ref "R9") (pin "2") (pinfunction "2_2") (pintype "passive"))
      (node (ref "U$3") (pin "B") (pinfunction "BLU_B") (pintype "bidirectional"))
    )
    (net (code "56") (name "Net-(U$3-GRN)") (class "Default")
      (node (ref "R10") (pin "2") (pinfunction "2_2") (pintype "passive"))
      (node (ref "U$3") (pin "G") (pinfunction "GRN_G") (pintype "bidirectional"))
    )
    (net (code "57") (name "Net-(U$3-RED)") (class "Default")
      (node (ref "R8") (pin "2") (pinfunction "2_2") (pintype "passive"))
      (node (ref "U$3") (pin "R") (pinfunction "RED_R") (pintype "bidirectional"))
    )
    (net (code "58") (name "Net-(U$4-+IN)") (class "Default")
      (node (ref "R14") (pin "1") (pinfunction "1_1") (pintype "passive"))
      (node (ref "R15") (pin "2") (pinfunction "2_2") (pintype "passive"))
      (node (ref "U$4") (pin "3") (pinfunction "+IN_3") (pintype "input"))
    )
    (net (code "59") (name "Net-(U1-D+)") (class "Default")
      (node (ref "R4") (pin "2") (pinfunction "2_2") (pintype "passive"))
      (node (ref "U1") (pin "21") (pinfunction "D+_21") (pintype "bidirectional"))
    )
    (net (code "60") (name "Net-(U1-D-)") (class "Default")
      (node (ref "R5") (pin "2") (pinfunction "2_2") (pintype "passive"))
      (node (ref "U1") (pin "20") (pinfunction "D-_20") (pintype "bidirectional"))
    )
    (net (code "61") (name "Net-(U1-X0)") (class "Default")
      (node (ref "U1") (pin "25") (pinfunction "X0_25") (pintype "bidirectional"))
      (node (ref "Y2") (pin "1") (pinfunction "1_1") (pintype "passive"))
    )
    (net (code "62") (name "Net-(U1-X1)") (class "Default")
      (node (ref "U1") (pin "24") (pinfunction "X1_24") (pintype "bidirectional"))
      (node (ref "Y2") (pin "3") (pinfunction "3_3") (pintype "passive"))
    )
    (net (code "63") (name "Net-(U2-BP)") (class "Default")
      (node (ref "C19") (pin "1") (pinfunction "1_1") (pintype "passive"))
      (node (ref "U2") (pin "4") (pinfunction "BP_4") (pintype "input"))
    )
    (net (code "64") (name "Net-(U3-BP)") (class "Default")
      (node (ref "C18") (pin "1") (pinfunction "1_1") (pintype "passive"))
      (node (ref "U3") (pin "4") (pinfunction "BP_4") (pintype "input"))
    )
    (net (code "65") (name "PWM1") (class "Default")
      (node (ref "MCU") (pin "15") (pinfunction "PH3(OC4A)_15") (pintype "bidirectional"))
    )
    (net (code "66") (name "PWM2") (class "Default")
      (node (ref "MCU") (pin "16") (pinfunction "PH4(OC4B)_16") (pintype "bidirectional"))
    )
    (net (code "67") (name "PWM3") (class "Default")
      (node (ref "MCU") (pin "17") (pinfunction "PH5(OC4C)_17") (pintype "bidirectional"))
    )
    (net (code "68") (name "RENCA") (class "Default")
      (node (ref "MCU") (pin "67") (pinfunction "PJ4(PCINT13)_67") (pintype "bidirectional"))
      (node (ref "RIGHT_MOTOR") (pin "3") (pinfunction "3_3") (pintype "passive"))
    )
    (net (code "69") (name "RENCB") (class "Default")
      (node (ref "MCU") (pin "66") (pinfunction "PJ3(PCINT12)_66") (pintype "bidirectional"))
      (node (ref "RIGHT_MOTOR") (pin "2") (pinfunction "2_2") (pintype "passive"))
    )
    (net (code "70") (name "RIN1") (class "Default")
      (node (ref "MCU") (pin "37") (pinfunction "PL2(T5)_37") (pintype "bidirectional"))
      (node (ref "U$1") (pin "17") (pinfunction "BIN1_17") (pintype "bidirectional"))
    )
    (net (code "71") (name "RIN2") (class "Default")
      (node (ref "MCU") (pin "38") (pinfunction "PL3(OC5A)_38") (pintype "bidirectional"))
      (node (ref "U$1") (pin "16") (pinfunction "BIN2_16") (pintype "bidirectional"))
    )
    (net (code "72") (name "RPWM") (class "Default")
      (node (ref "MCU") (pin "40") (pinfunction "PL5(OC5C)_40") (pintype "bidirectional"))
      (node (ref "U$1") (pin "15") (pinfunction "PWMB_15") (pintype "bidirectional"))
    )
    (net (code "73") (name "RX0") (class "Default")
      (node (ref "FTDI") (pin "3") (pinfunction "TXO_3") (pintype "passive"))
      (node (ref "MCU") (pin "2") (pinfunction "(RXD0/PCIN8)PE0_2") (pintype "bidirectional"))
    )
    (net (code "74") (name "RX1") (class "Default")
      (node (ref "MCU") (pin "45") (pinfunction "(RXD1/INT2)PD2_45") (pintype "bidirectional"))
    )
    (net (code "75") (name "R_LED") (class "Default")
      (node (ref "MCU") (pin "7") (pinfunction "(OC3C/INT5)PE5_7") (pintype "bidirectional"))
      (node (ref "R8") (pin "1") (pinfunction "1_1") (pintype "passive"))
    )
    (net (code "76") (name "SCL") (class "Default")
      (node (ref "MCU") (pin "43") (pinfunction "(SCL/INT0)PD0_43") (pintype "bidirectional"))
      (node (ref "R24") (pin "1") (pinfunction "1_1") (pintype "passive"))
      (node (ref "U$5") (pin "D2") (pinfunction "D_D2") (pintype "passive"))
    )
    (net (code "77") (name "SDA") (class "Default")
      (node (ref "MCU") (pin "44") (pinfunction "(SDA/INT1)PD1_44") (pintype "bidirectional"))
      (node (ref "R24") (pin "2") (pinfunction "1_2") (pintype "passive"))
      (node (ref "U$5") (pin "D1") (pinfunction "D_D1") (pintype "passive"))
    )
    (net (code "78") (name "STBY") (class "Default")
      (node (ref "MCU") (pin "41") (pinfunction "PL6_41") (pintype "bidirectional"))
      (node (ref "U$2") (pin "2") (pinfunction "B_2") (pintype "bidirectional"))
    )
    (net (code "79") (name "TX0") (class "Default")
      (node (ref "FTDI") (pin "2") (pinfunction "RXI_2") (pintype "passive"))
      (node (ref "MCU") (pin "3") (pinfunction "(TXD0)PE1_3") (pintype "bidirectional"))
    )
    (net (code "80") (name "TX1") (class "Default")
      (node (ref "MCU") (pin "46") (pinfunction "(TXD1/INT3)PD3_46") (pintype "bidirectional"))
    )
    (net (code "81") (name "VCC") (class "Default")
      (node (ref "C1") (pin "+") (pinfunction "+_+") (pintype "passive"))
      (node (ref "C2") (pin "+") (pinfunction "+_+") (pintype "passive"))
      (node (ref "C3") (pin "1") (pinfunction "1_1") (pintype "passive"))
      (node (ref "C4") (pin "1") (pinfunction "1_1") (pintype "passive"))
      (node (ref "Q2") (pin "2") (pinfunction "S_2") (pintype "passive"))
      (node (ref "R14") (pin "2") (pinfunction "2_2") (pintype "passive"))
      (node (ref "R16") (pin "2") (pinfunction "2_2") (pintype "passive"))
      (node (ref "U$1") (pin "13") (pinfunction "VM2_13") (pintype "bidirectional"))
      (node (ref "U$1") (pin "14") (pinfunction "VM3_14") (pintype "bidirectional"))
      (node (ref "U$1") (pin "24") (pinfunction "VM1_24") (pintype "bidirectional"))
      (node (ref "U2") (pin "1") (pinfunction "IN_1") (pintype "input"))
      (node (ref "U2") (pin "3") (pinfunction "EN_3") (pintype "input"))
    )
    (net (code "82") (name "V_BATT") (class "Default")
      (node (ref "D1") (pin "A") (pinfunction "A_A") (pintype "passive"))
      (node (ref "R18") (pin "2") (pinfunction "2_2") (pintype "passive"))
    )
    (net (code "83") (name "V_COMP") (class "Default")
      (node (ref "U$2") (pin "1") (pinfunction "A_1") (pintype "bidirectional"))
      (node (ref "U$4") (pin "1") (pinfunction "OUT_1") (pintype "output"))
    )
    (net (code "84") (name "unconnected-(MCU-(A8)PC0-Pad53)") (class "Default")
      (node (ref "MCU") (pin "53") (pinfunction "(A8)PC0_53") (pintype "bidirectional"))
    )
    (net (code "85") (name "unconnected-(MCU-(A9)PC1-Pad54)") (class "Default")
      (node (ref "MCU") (pin "54") (pinfunction "(A9)PC1_54") (pintype "bidirectional"))
    )
    (net (code "86") (name "unconnected-(MCU-(A10)PC2-Pad55)") (class "Default")
      (node (ref "MCU") (pin "55") (pinfunction "(A10)PC2_55") (pintype "bidirectional"))
    )
    (net (code "87") (name "unconnected-(MCU-(A11)PC3-Pad56)") (class "Default")
      (node (ref "MCU") (pin "56") (pinfunction "(A11)PC3_56") (pintype "bidirectional"))
    )
    (net (code "88") (name "unconnected-(MCU-(A12)PC4-Pad57)") (class "Default")
      (node (ref "MCU") (pin "57") (pinfunction "(A12)PC4_57") (pintype "bidirectional"))
    )
    (net (code "89") (name "unconnected-(MCU-(A13)PC5-Pad58)") (class "Default")
      (node (ref "MCU") (pin "58") (pinfunction "(A13)PC5_58") (pintype "bidirectional"))
    )
    (net (code "90") (name "unconnected-(MCU-(A14)PC6-Pad59)") (class "Default")
      (node (ref "MCU") (pin "59") (pinfunction "(A14)PC6_59") (pintype "bidirectional"))
    )
    (net (code "91") (name "unconnected-(MCU-(A15)PC7-Pad60)") (class "Default")
      (node (ref "MCU") (pin "60") (pinfunction "(A15)PC7_60") (pintype "bidirectional"))
    )
    (net (code "92") (name "unconnected-(MCU-(AD0)PA0-Pad78)") (class "Default")
      (node (ref "MCU") (pin "78") (pinfunction "(AD0)PA0_78") (pintype "bidirectional"))
    )
    (net (code "93") (name "unconnected-(MCU-(AD1)PA1-Pad77)") (class "Default")
      (node (ref "MCU") (pin "77") (pinfunction "(AD1)PA1_77") (pintype "bidirectional"))
    )
    (net (code "94") (name "unconnected-(MCU-(AD2)PA2-Pad76)") (class "Default")
      (node (ref "MCU") (pin "76") (pinfunction "(AD2)PA2_76") (pintype "bidirectional"))
    )
    (net (code "95") (name "unconnected-(MCU-(AD3)PA3-Pad75)") (class "Default")
      (node (ref "MCU") (pin "75") (pinfunction "(AD3)PA3_75") (pintype "bidirectional"))
    )
    (net (code "96") (name "unconnected-(MCU-(AD4)PA4-Pad74)") (class "Default")
      (node (ref "MCU") (pin "74") (pinfunction "(AD4)PA4_74") (pintype "bidirectional"))
    )
    (net (code "97") (name "unconnected-(MCU-(AD5)PA5-Pad73)") (class "Default")
      (node (ref "MCU") (pin "73") (pinfunction "(AD5)PA5_73") (pintype "bidirectional"))
    )
    (net (code "98") (name "unconnected-(MCU-(AD6)PA6-Pad72)") (class "Default")
      (node (ref "MCU") (pin "72") (pinfunction "(AD6)PA6_72") (pintype "bidirectional"))
    )
    (net (code "99") (name "unconnected-(MCU-(AD7)PA7-Pad71)") (class "Default")
      (node (ref "MCU") (pin "71") (pinfunction "(AD7)PA7_71") (pintype "bidirectional"))
    )
    (net (code "100") (name "unconnected-(MCU-(ADC0)PF0-Pad97)") (class "Default")
      (node (ref "MCU") (pin "97") (pinfunction "(ADC0)PF0_97") (pintype "bidirectional"))
    )
    (net (code "101") (name "unconnected-(MCU-(ADC1)PF1-Pad96)") (class "Default")
      (node (ref "MCU") (pin "96") (pinfunction "(ADC1)PF1_96") (pintype "bidirectional"))
    )
    (net (code "102") (name "unconnected-(MCU-(ADC2)PF2-Pad95)") (class "Default")
      (node (ref "MCU") (pin "95") (pinfunction "(ADC2)PF2_95") (pintype "bidirectional"))
    )
    (net (code "103") (name "unconnected-(MCU-(ADC3)PF3-Pad94)") (class "Default")
      (node (ref "MCU") (pin "94") (pinfunction "(ADC3)PF3_94") (pintype "bidirectional"))
    )
    (net (code "104") (name "unconnected-(MCU-(ADC4{slash}TCK)PF4-Pad93)") (class "Default")
      (node (ref "MCU") (pin "93") (pinfunction "(ADC4/TCK)PF4_93") (pintype "bidirectional"))
    )
    (net (code "105") (name "unconnected-(MCU-(ADC5{slash}TMS)PF5-Pad92)") (class "Default")
      (node (ref "MCU") (pin "92") (pinfunction "(ADC5/TMS)PF5_92") (pintype "bidirectional"))
    )
    (net (code "106") (name "unconnected-(MCU-(ADC6{slash}TDO)PF6-Pad91)") (class "Default")
      (node (ref "MCU") (pin "91") (pinfunction "(ADC6/TDO)PF6_91") (pintype "bidirectional"))
    )
    (net (code "107") (name "unconnected-(MCU-(ADC7{slash}TDI)PF7-Pad90)") (class "Default")
      (node (ref "MCU") (pin "90") (pinfunction "(ADC7/TDI)PF7_90") (pintype "bidirectional"))
    )
    (net (code "108") (name "unconnected-(MCU-(ALE)PG2-Pad70)") (class "Default")
      (node (ref "MCU") (pin "70") (pinfunction "(ALE)PG2_70") (pintype "bidirectional"))
    )
    (net (code "109") (name "unconnected-(MCU-(ICP1)PD4-Pad47)") (class "Default")
      (node (ref "MCU") (pin "47") (pinfunction "(ICP1)PD4_47") (pintype "bidirectional"))
    )
    (net (code "110") (name "unconnected-(MCU-(OC0A{slash}OC1C{slash}PCINT7)PB7-Pad26)") (class "Default")
      (node (ref "MCU") (pin "26") (pinfunction "(OC0A/OC1C/PCINT7)PB7_26") (pintype "bidirectional"))
    )
    (net (code "111") (name "unconnected-(MCU-(OC1A{slash}PCINT5)PB5-Pad24)") (class "Default")
      (node (ref "MCU") (pin "24") (pinfunction "(OC1A/PCINT5)PB5_24") (pintype "bidirectional"))
    )
    (net (code "112") (name "unconnected-(MCU-(OC1B{slash}PCINT6)PB6-Pad25)") (class "Default")
      (node (ref "MCU") (pin "25") (pinfunction "(OC1B/PCINT6)PB6_25") (pintype "bidirectional"))
    )
    (net (code "113") (name "unconnected-(MCU-(OC2A{slash}PCINT4)PB4-Pad23)") (class "Default")
      (node (ref "MCU") (pin "23") (pinfunction "(OC2A/PCINT4)PB4_23") (pintype "bidirectional"))
    )
    (net (code "114") (name "unconnected-(MCU-(RD)PG1-Pad52)") (class "Default")
      (node (ref "MCU") (pin "52") (pinfunction "(RD)PG1_52") (pintype "bidirectional"))
    )
    (net (code "115") (name "unconnected-(MCU-(T0)PD7-Pad50)") (class "Default")
      (node (ref "MCU") (pin "50") (pinfunction "(T0)PD7_50") (pintype "bidirectional"))
    )
    (net (code "116") (name "unconnected-(MCU-(T1)PD6-Pad49)") (class "Default")
      (node (ref "MCU") (pin "49") (pinfunction "(T1)PD6_49") (pintype "bidirectional"))
    )
    (net (code "117") (name "unconnected-(MCU-(TOSC1)PG4-Pad29)") (class "Default")
      (node (ref "MCU") (pin "29") (pinfunction "(TOSC1)PG4_29") (pintype "bidirectional"))
    )
    (net (code "118") (name "unconnected-(MCU-(TOSC2)PG3-Pad28)") (class "Default")
      (node (ref "MCU") (pin "28") (pinfunction "(TOSC2)PG3_28") (pintype "bidirectional"))
    )
    (net (code "119") (name "unconnected-(MCU-(WR)PG0-Pad51)") (class "Default")
      (node (ref "MCU") (pin "51") (pinfunction "(WR)PG0_51") (pintype "bidirectional"))
    )
    (net (code "120") (name "unconnected-(MCU-(XCK0{slash}AIN0)PE2-Pad4)") (class "Default")
      (node (ref "MCU") (pin "4") (pinfunction "(XCK0/AIN0)PE2_4") (pintype "bidirectional"))
    )
    (net (code "121") (name "unconnected-(MCU-(XCK1)PD5-Pad48)") (class "Default")
      (node (ref "MCU") (pin "48") (pinfunction "(XCK1)PD5_48") (pintype "bidirectional"))
    )
    (net (code "122") (name "unconnected-(MCU-PH0(RXD2)-Pad12)") (class "Default")
      (node (ref "MCU") (pin "12") (pinfunction "PH0(RXD2)_12") (pintype "bidirectional"))
    )
    (net (code "123") (name "unconnected-(MCU-PH1(TXD2)-Pad13)") (class "Default")
      (node (ref "MCU") (pin "13") (pinfunction "PH1(TXD2)_13") (pintype "bidirectional"))
    )
    (net (code "124") (name "unconnected-(MCU-PH2(XCK2)-Pad14)") (class "Default")
      (node (ref "MCU") (pin "14") (pinfunction "PH2(XCK2)_14") (pintype "bidirectional"))
    )
    (net (code "125") (name "unconnected-(MCU-PH6(OC2B)-Pad18)") (class "Default")
      (node (ref "MCU") (pin "18") (pinfunction "PH6(OC2B)_18") (pintype "bidirectional"))
    )
    (net (code "126") (name "unconnected-(MCU-PH7(T4)-Pad27)") (class "Default")
      (node (ref "MCU") (pin "27") (pinfunction "PH7(T4)_27") (pintype "bidirectional"))
    )
    (net (code "127") (name "unconnected-(MCU-PJ0(RXD3{slash}PCINT9)-Pad63)") (class "Default")
      (node (ref "MCU") (pin "63") (pinfunction "PJ0(RXD3/PCINT9)_63") (pintype "bidirectional"))
    )
    (net (code "128") (name "unconnected-(MCU-PJ1(TXD3{slash}PCINT10)-Pad64)") (class "Default")
      (node (ref "MCU") (pin "64") (pinfunction "PJ1(TXD3/PCINT10)_64") (pintype "bidirectional"))
    )
    (net (code "129") (name "unconnected-(MCU-PJ2(XCK3{slash}PCINT11)-Pad65)") (class "Default")
      (node (ref "MCU") (pin "65") (pinfunction "PJ2(XCK3/PCINT11)_65") (pintype "bidirectional"))
    )
    (net (code "130") (name "unconnected-(MCU-PJ7-Pad79)") (class "Default")
      (node (ref "MCU") (pin "79") (pinfunction "PJ7_79") (pintype "bidirectional"))
    )
    (net (code "131") (name "unconnected-(MCU-PL7-Pad42)") (class "Default")
      (node (ref "MCU") (pin "42") (pinfunction "PL7_42") (pintype "bidirectional"))
    )
    (net (code "132") (name "unconnected-(U$4-V+-Pad5)") (class "Default")
      (node (ref "U$4") (pin "5") (pinfunction "V+_5") (pintype "power_in"))
    )
    (net (code "133") (name "unconnected-(U$4-V--Pad2)") (class "Default")
      (node (ref "U$4") (pin "2") (pinfunction "V-_2") (pintype "power_in"))
    )
    (net (code "134") (name "unconnected-(U1-GOUT0-Pad4)") (class "Default")
      (node (ref "U1") (pin "4") (pinfunction "GOUT0_4") (pintype "bidirectional"))
    )
    (net (code "135") (name "unconnected-(U1-GOUT1-Pad5)") (class "Default")
      (node (ref "U1") (pin "5") (pinfunction "GOUT1_5") (pintype "bidirectional"))
    )
    (net (code "136") (name "unconnected-(U1-GOUT2-Pad6)") (class "Default")
      (node (ref "U1") (pin "6") (pinfunction "GOUT2_6") (pintype "bidirectional"))
    )
    (net (code "137") (name "unconnected-(U1-GOUT3-Pad7)") (class "Default")
      (node (ref "U1") (pin "7") (pinfunction "GOUT3_7") (pintype "bidirectional"))
    )
    (net (code "138") (name "unconnected-(U1-GOUT4-Pad8)") (class "Default")
      (node (ref "U1") (pin "8") (pinfunction "GOUT4_8") (pintype "bidirectional"))
    )
    (net (code "139") (name "unconnected-(U1-GOUT5-Pad9)") (class "Default")
      (node (ref "U1") (pin "9") (pinfunction "GOUT5_9") (pintype "bidirectional"))
    )
    (net (code "140") (name "unconnected-(U1-GOUT6-Pad10)") (class "Default")
      (node (ref "U1") (pin "10") (pinfunction "GOUT6_10") (pintype "bidirectional"))
    )
    (net (code "141") (name "unconnected-(U1-GOUT7-Pad11)") (class "Default")
      (node (ref "U1") (pin "11") (pinfunction "GOUT7_11") (pintype "bidirectional"))
    )
    (net (code "142") (name "unconnected-(U1-GPIN0-Pad26)") (class "Default")
      (node (ref "U1") (pin "26") (pinfunction "GPIN0_26") (pintype "bidirectional"))
    )
    (net (code "143") (name "unconnected-(U1-GPIN1-Pad27)") (class "Default")
      (node (ref "U1") (pin "27") (pinfunction "GPIN1_27") (pintype "bidirectional"))
    )
    (net (code "144") (name "unconnected-(U1-GPIN2-Pad28)") (class "Default")
      (node (ref "U1") (pin "28") (pinfunction "GPIN2_28") (pintype "bidirectional"))
    )
    (net (code "145") (name "unconnected-(U1-GPIN3-Pad29)") (class "Default")
      (node (ref "U1") (pin "29") (pinfunction "GPIN3_29") (pintype "bidirectional"))
    )
    (net (code "146") (name "unconnected-(U1-GPIN4-Pad30)") (class "Default")
      (node (ref "U1") (pin "30") (pinfunction "GPIN4_30") (pintype "bidirectional"))
    )
    (net (code "147") (name "unconnected-(U1-GPIN5-Pad31)") (class "Default")
      (node (ref "U1") (pin "31") (pinfunction "GPIN5_31") (pintype "bidirectional"))
    )
    (net (code "148") (name "unconnected-(U1-GPIN6-Pad32)") (class "Default")
      (node (ref "U1") (pin "32") (pinfunction "GPIN6_32") (pintype "bidirectional"))
    )
    (net (code "149") (name "unconnected-(U1-GPIN7-Pad1)") (class "Default")
      (node (ref "U1") (pin "1") (pinfunction "GPIN7_1") (pintype "bidirectional"))
    )
    (net (code "150") (name "unconnected-(U1-GPX-Pad17)") (class "Default")
      (node (ref "U1") (pin "17") (pinfunction "GPX_17") (pintype "bidirectional"))
    )
    (net (code "151") (name "unconnected-(U1-VBCOMP-Pad22)") (class "Default")
      (node (ref "U1") (pin "22") (pinfunction "VBCOMP_22") (pintype "bidirectional"))
    )
  )
)
